# Reader_3_0.net
KiCad netlist of a schematic drawn in EAGLE
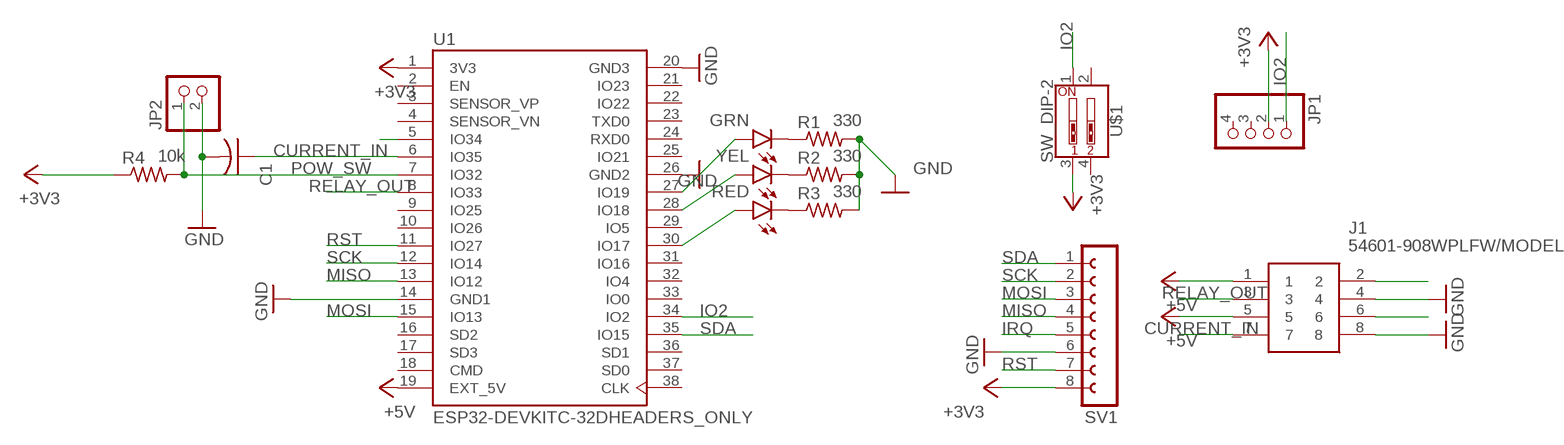
[diagram p0: schematic, sheet 1]

(export (version "E")
  (design (tool "Eeschema 10.0.6"))
  (components
    (comp (ref "C1")
      (value "C-US025-025X050")
      (footprint "eagle-import:C025-025X050")
      (libsource (lib "eagle-import") (part "C-US025-025X050"))
    )
    (comp (ref "GRN")
      (value "LED5MM")
      (footprint "eagle-import:LED5MM")
      (libsource (lib "eagle-import") (part "LED5MM"))
    )
    (comp (ref "J1")
      (value "54601-908WPLFW/MODEL")
      (footprint "eagle-import:HDRV4W64P254_1X4_1016X508X838B")
      (libsource (lib "eagle-import") (part "54601-908WPLFW/MODEL"))
    )
    (comp (ref "JP1")
      (value "PINHD-1X4/90")
      (footprint "eagle-import:1X04_90")
      (libsource (lib "eagle-import") (part "PINHD-1X4/90"))
    )
    (comp (ref "JP2")
      (value "PINHD-1X2/90")
      (footprint "eagle-import:1X02_90")
      (libsource (lib "eagle-import") (part "PINHD-1X2/90"))
    )
    (comp (ref "R1")
      (value "330")
      (footprint "eagle-import:0204_7")
      (libsource (lib "eagle-import") (part "R-US"))
    )
    (comp (ref "R2")
      (value "330")
      (footprint "eagle-import:0204_7")
      (libsource (lib "eagle-import") (part "R-US"))
    )
    (comp (ref "R3")
      (value "330")
      (footprint "eagle-import:0204_7")
      (libsource (lib "eagle-import") (part "R-US"))
    )
    (comp (ref "R4")
      (value "10k")
      (footprint "eagle-import:0204_7")
      (libsource (lib "eagle-import") (part "R-US"))
    )
    (comp (ref "RED")
      (value "LED5MM")
      (footprint "eagle-import:LED5MM")
      (libsource (lib "eagle-import") (part "LED5MM"))
    )
    (comp (ref "SV1")
      (value "FE08-1")
      (footprint "eagle-import:HDR_F_1X8")
      (libsource (lib "eagle-import") (part "FE08-1"))
    )
    (comp (ref "U$1")
      (value "SW_DIP-2")
      (footprint "eagle-import:SW_DIP-2")
      (libsource (lib "eagle-import") (part "SW_DIP-2"))
    )
    (comp (ref "U1")
      (value "ESP32-DEVKITC-32DHEADERS_ONLY")
      (footprint "eagle-import:ESP32_DEVKITC_DIP")
      (fields (field (name "SPICEPREFIX") "X"))
      (libsource (lib "eagle-import") (part "ESP32-DEVKITC-32DHEADERS_ONLY"))
    )
    (comp (ref "YEL")
      (value "LED5MM")
      (footprint "eagle-import:LED5MM")
      (libsource (lib "eagle-import") (part "LED5MM"))
    )
  )
  (nets
    (net (code "1") (name "+3V3") (class "Default")
      (node (ref "JP1") (pin "2") (pinfunction "2_2") (pintype "passive"))
      (node (ref "R4") (pin "1") (pinfunction "1_1") (pintype "passive"))
      (node (ref "SV1") (pin "8") (pinfunction "8_8") (pintype "passive"))
      (node (ref "U$1") (pin "3") (pinfunction "3_3") (pintype "passive"))
      (node (ref "U1") (pin "1") (pinfunction "3V3_1") (pintype "power_in"))
    )
    (net (code "2") (name "+5V") (class "Default")
      (node (ref "J1") (pin "1") (pinfunction "1_1") (pintype "bidirectional"))
      (node (ref "J1") (pin "5") (pinfunction "5_5") (pintype "bidirectional"))
      (node (ref "U1") (pin "19") (pinfunction "EXT_5V_19") (pintype "power_in"))
    )
    (net (code "3") (name "/CURRENT_IN") (class "Default")
      (node (ref "C1") (pin "1") (pinfunction "1_1") (pintype "passive"))
      (node (ref "J1") (pin "7") (pinfunction "7_7") (pintype "bidirectional"))
      (node (ref "U1") (pin "6") (pinfunction "IO35_6") (pintype "bidirectional"))
    )
    (net (code "4") (name "/IO2") (class "Default")
      (node (ref "JP1") (pin "1") (pinfunction "1_1") (pintype "passive"))
      (node (ref "U$1") (pin "1") (pinfunction "1_1") (pintype "passive"))
      (node (ref "U1") (pin "34") (pinfunction "IO2_34") (pintype "bidirectional"))
    )
    (net (code "5") (name "/IRQ") (class "Default")
      (node (ref "SV1") (pin "5") (pinfunction "5_5") (pintype "passive"))
    )
    (net (code "6") (name "/MISO") (class "Default")
      (node (ref "SV1") (pin "4") (pinfunction "4_4") (pintype "passive"))
      (node (ref "U1") (pin "13") (pinfunction "IO12_13") (pintype "bidirectional"))
    )
    (net (code "7") (name "/MOSI") (class "Default")
      (node (ref "SV1") (pin "3") (pinfunction "3_3") (pintype "passive"))
      (node (ref "U1") (pin "15") (pinfunction "IO13_15") (pintype "bidirectional"))
    )
    (net (code "8") (name "/POW_SW") (class "Default")
      (node (ref "JP2") (pin "1") (pinfunction "1_1") (pintype "passive"))
      (node (ref "R4") (pin "2") (pinfunction "2_2") (pintype "passive"))
      (node (ref "U1") (pin "7") (pinfunction "IO32_7") (pintype "bidirectional"))
    )
    (net (code "9") (name "/RELAY_OUT") (class "Default")
      (node (ref "J1") (pin "3") (pinfunction "3_3") (pintype "bidirectional"))
      (node (ref "U1") (pin "8") (pinfunction "IO33_8") (pintype "bidirectional"))
    )
    (net (code "10") (name "/RST") (class "Default")
      (node (ref "SV1") (pin "7") (pinfunction "7_7") (pintype "passive"))
      (node (ref "U1") (pin "11") (pinfunction "IO27_11") (pintype "bidirectional"))
    )
    (net (code "11") (name "/SCK") (class "Default")
      (node (ref "SV1") (pin "2") (pinfunction "2_2") (pintype "passive"))
      (node (ref "U1") (pin "12") (pinfunction "IO14_12") (pintype "bidirectional"))
    )
    (net (code "12") (name "/SDA") (class "Default")
      (node (ref "SV1") (pin "1") (pinfunction "1_1") (pintype "passive"))
      (node (ref "U1") (pin "35") (pinfunction "IO15_35") (pintype "bidirectional"))
    )
    (net (code "13") (name "GND") (class "Default")
      (node (ref "C1") (pin "2") (pinfunction "2_2") (pintype "passive"))
      (node (ref "J1") (pin "4") (pinfunction "4_4") (pintype "bidirectional"))
      (node (ref "J1") (pin "8") (pinfunction "8_8") (pintype "bidirectional"))
      (node (ref "JP2") (pin "2") (pinfunction "2_2") (pintype "passive"))
      (node (ref "R1") (pin "2") (pinfunction "2_2") (pintype "passive"))
      (node (ref "R2") (pin "2") (pinfunction "2_2") (pintype "passive"))
      (node (ref "R3") (pin "2") (pinfunction "2_2") (pintype "passive"))
      (node (ref "SV1") (pin "6") (pinfunction "6_6") (pintype "passive"))
      (node (ref "U1") (pin "14") (pinfunction "GND1_14") (pintype "power_in"))
      (node (ref "U1") (pin "20") (pinfunction "GND3_20") (pintype "power_in"))
      (node (ref "U1") (pin "26") (pinfunction "GND2_26") (pintype "power_in"))
    )
    (net (code "14") (name "Net-(GRN-C)") (class "Default")
      (node (ref "GRN") (pin "K") (pinfunction "C_K") (pintype "passive"))
      (node (ref "R1") (pin "1") (pinfunction "1_1") (pintype "passive"))
    )
    (net (code "15") (name "Net-(RED-C)") (class "Default")
      (node (ref "R3") (pin "1") (pinfunction "1_1") (pintype "passive"))
      (node (ref "RED") (pin "K") (pinfunction "C_K") (pintype "passive"))
    )
    (net (code "16") (name "Net-(U1-IO17)") (class "Default")
      (node (ref "RED") (pin "A") (pinfunction "A_A") (pintype "passive"))
      (node (ref "U1") (pin "30") (pinfunction "IO17_30") (pintype "bidirectional"))
    )
    (net (code "17") (name "Net-(U1-IO18)") (class "Default")
      (node (ref "U1") (pin "28") (pinfunction "IO18_28") (pintype "bidirectional"))
      (node (ref "YEL") (pin "A") (pinfunction "A_A") (pintype "passive"))
    )
    (net (code "18") (name "Net-(U1-IO19)") (class "Default")
      (node (ref "GRN") (pin "A") (pinfunction "A_A") (pintype "passive"))
      (node (ref "U1") (pin "27") (pinfunction "IO19_27") (pintype "bidirectional"))
    )
    (net (code "19") (name "Net-(YEL-C)") (class "Default")
      (node (ref "R2") (pin "1") (pinfunction "1_1") (pintype "passive"))
      (node (ref "YEL") (pin "K") (pinfunction "C_K") (pintype "passive"))
    )
    (net (code "20") (name "unconnected-(J1-Pad2)") (class "Default")
      (node (ref "J1") (pin "2") (pinfunction "2_2") (pintype "bidirectional"))
    )
    (net (code "21") (name "unconnected-(J1-Pad6)") (class "Default")
      (node (ref "J1") (pin "6") (pinfunction "6_6") (pintype "bidirectional"))
    )
    (net (code "22") (name "unconnected-(JP1-Pad3)") (class "Default")
      (node (ref "JP1") (pin "3") (pinfunction "3_3") (pintype "passive"))
    )
    (net (code "23") (name "unconnected-(JP1-Pad4)") (class "Default")
      (node (ref "JP1") (pin "4") (pinfunction "4_4") (pintype "passive"))
    )
    (net (code "24") (name "unconnected-(U$1-Pad2)") (class "Default")
      (node (ref "U$1") (pin "2") (pinfunction "2_2") (pintype "passive"))
    )
    (net (code "25") (name "unconnected-(U$1-Pad4)") (class "Default")
      (node (ref "U$1") (pin "4") (pinfunction "4_4") (pintype "passive"))
    )
    (net (code "26") (name "unconnected-(U1-CLK-Pad38)") (class "Default")
      (node (ref "U1") (pin "38") (pinfunction "CLK_38") (pintype "input"))
    )
    (net (code "27") (name "unconnected-(U1-CMD-Pad18)") (class "Default")
      (node (ref "U1") (pin "18") (pinfunction "CMD_18") (pintype "bidirectional"))
    )
    (net (code "28") (name "unconnected-(U1-EN-Pad2)") (class "Default")
      (node (ref "U1") (pin "2") (pinfunction "EN_2") (pintype "input"))
    )
    (net (code "29") (name "unconnected-(U1-IO0-Pad33)") (class "Default")
      (node (ref "U1") (pin "33") (pinfunction "IO0_33") (pintype "bidirectional"))
    )
    (net (code "30") (name "unconnected-(U1-IO4-Pad32)") (class "Default")
      (node (ref "U1") (pin "32") (pinfunction "IO4_32") (pintype "bidirectional"))
    )
    (net (code "31") (name "unconnected-(U1-IO5-Pad29)") (class "Default")
      (node (ref "U1") (pin "29") (pinfunction "IO5_29") (pintype "bidirectional"))
    )
    (net (code "32") (name "unconnected-(U1-IO16-Pad31)") (class "Default")
      (node (ref "U1") (pin "31") (pinfunction "IO16_31") (pintype "bidirectional"))
    )
    (net (code "33") (name "unconnected-(U1-IO21-Pad25)") (class "Default")
      (node (ref "U1") (pin "25") (pinfunction "IO21_25") (pintype "bidirectional"))
    )
    (net (code "34") (name "unconnected-(U1-IO22-Pad22)") (class "Default")
      (node (ref "U1") (pin "22") (pinfunction "IO22_22") (pintype "bidirectional"))
    )
    (net (code "35") (name "unconnected-(U1-IO23-Pad21)") (class "Default")
      (node (ref "U1") (pin "21") (pinfunction "IO23_21") (pintype "bidirectional"))
    )
    (net (code "36") (name "unconnected-(U1-IO25-Pad9)") (class "Default")
      (node (ref "U1") (pin "9") (pinfunction "IO25_9") (pintype "bidirectional"))
    )
    (net (code "37") (name "unconnected-(U1-IO26-Pad10)") (class "Default")
      (node (ref "U1") (pin "10") (pinfunction "IO26_10") (pintype "bidirectional"))
    )
    (net (code "38") (name "unconnected-(U1-IO34-Pad5)") (class "Default")
      (node (ref "U1") (pin "5") (pinfunction "IO34_5") (pintype "bidirectional"))
    )
    (net (code "39") (name "unconnected-(U1-RXD0-Pad24)") (class "Default")
      (node (ref "U1") (pin "24") (pinfunction "RXD0_24") (pintype "input"))
    )
    (net (code "40") (name "unconnected-(U1-SD0-Pad37)") (class "Default")
      (node (ref "U1") (pin "37") (pinfunction "SD0_37") (pintype "bidirectional"))
    )
    (net (code "41") (name "unconnected-(U1-SD1-Pad36)") (class "Default")
      (node (ref "U1") (pin "36") (pinfunction "SD1_36") (pintype "bidirectional"))
    )
    (net (code "42") (name "unconnected-(U1-SD2-Pad16)") (class "Default")
      (node (ref "U1") (pin "16") (pinfunction "SD2_16") (pintype "bidirectional"))
    )
    (net (code "43") (name "unconnected-(U1-SD3-Pad17)") (class "Default")
      (node (ref "U1") (pin "17") (pinfunction "SD3_17") (pintype "bidirectional"))
    )
    (net (code "44") (name "unconnected-(U1-SENSOR_VN-Pad4)") (class "Default")
      (node (ref "U1") (pin "4") (pinfunction "SENSOR_VN_4") (pintype "input"))
    )
    (net (code "45") (name "unconnected-(U1-SENSOR_VP-Pad3)") (class "Default")
      (node (ref "U1") (pin "3") (pinfunction "SENSOR_VP_3") (pintype "input"))
    )
    (net (code "46") (name "unconnected-(U1-TXD0-Pad23)") (class "Default")
      (node (ref "U1") (pin "23") (pinfunction "TXD0_23") (pintype "output"))
    )
  )
)
